# EasyEDA_ir-rgb-controller-chematic.net
KiCad netlist of a schematic drawn in EasyEDA
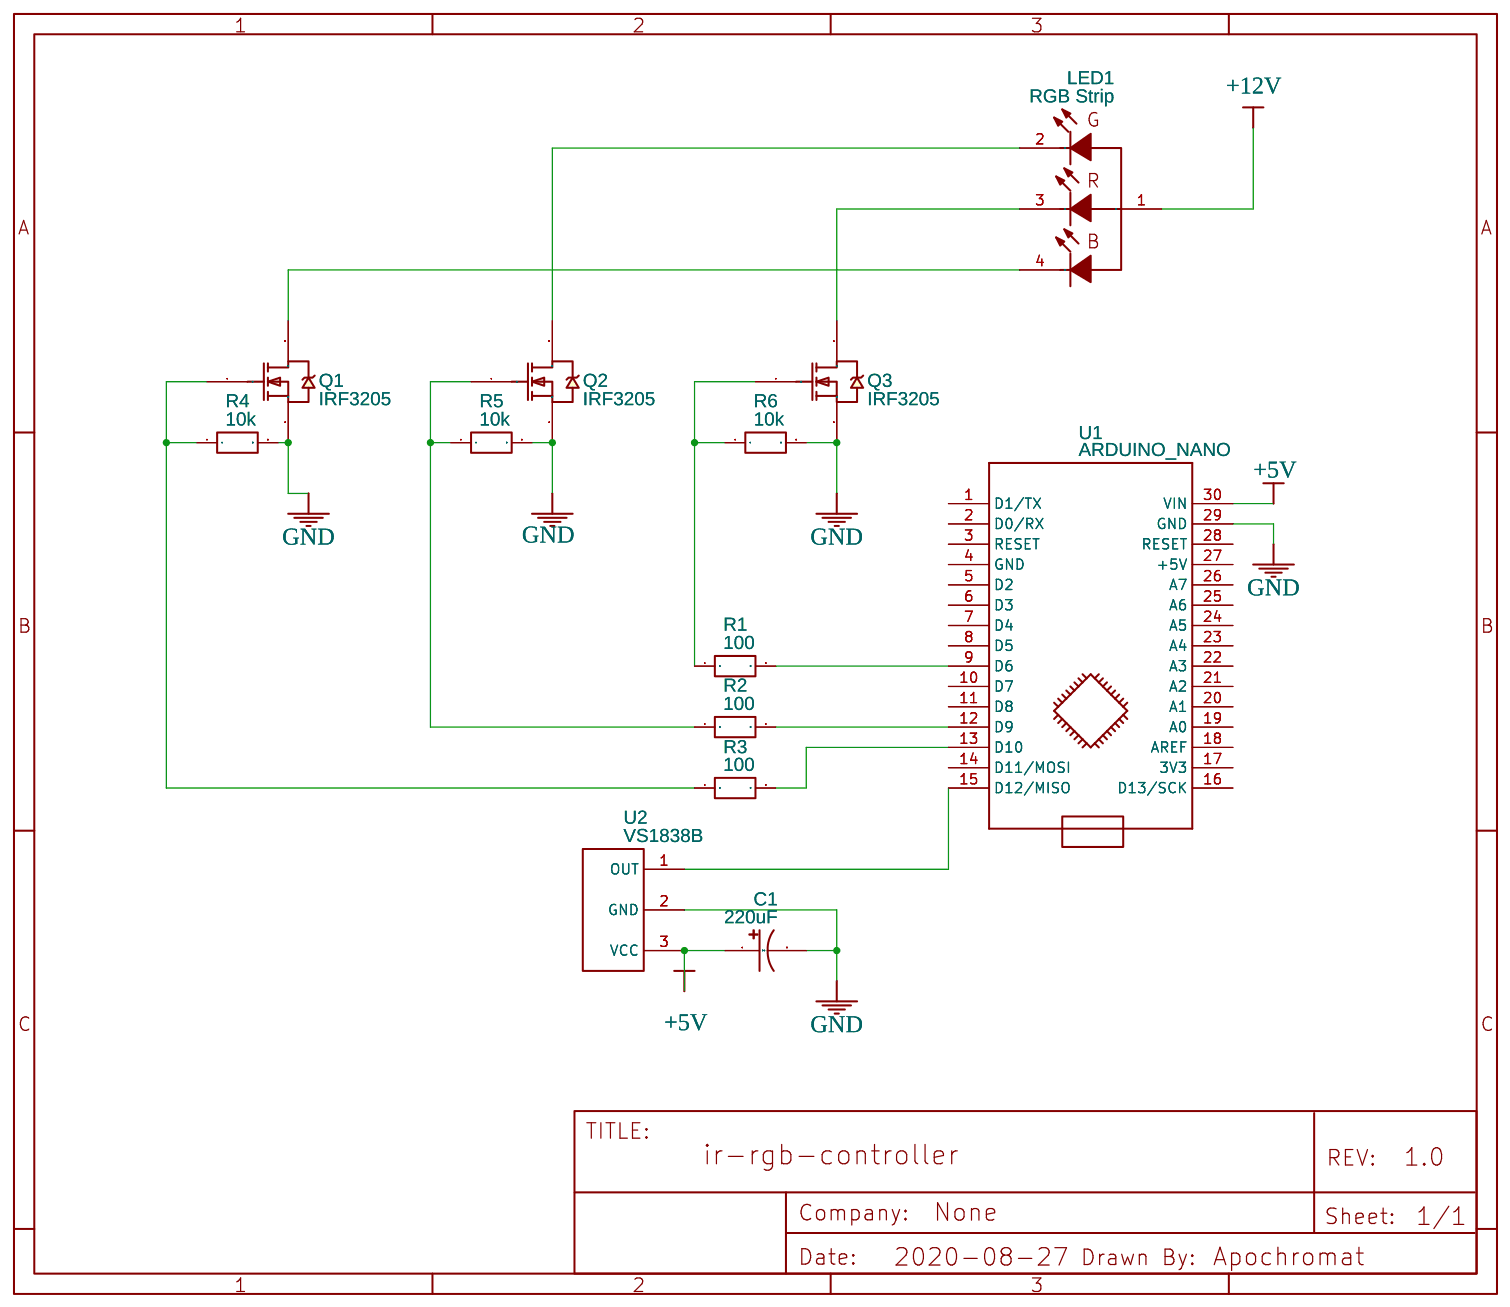
[diagram p0: schematic sheet]

(export (version "E")
  (design (tool "Eeschema 10.0.6"))
  (components
    (comp (ref "C1")
      (value "220uF")
      (fields (field (name "BOM_Supplier Part") "C165659"))
      (libsource (lib "") (part "NHA 25V220uF"))
    )
    (comp (ref "LED1") (value "RGB Strip") (libsource (lib "") (part "RGB Strip")))
    (comp (ref "Q1") (value "IRF3205") (libsource (lib "") (part "IRF3205")))
    (comp (ref "Q2") (value "IRF3205") (libsource (lib "") (part "IRF3205")))
    (comp (ref "Q3") (value "IRF3205") (libsource (lib "") (part "IRF3205")))
    (comp (ref "R1") (value "100") (libsource (lib "") (part "R_AXIAL-0.4_EU")))
    (comp (ref "R2") (value "100") (libsource (lib "") (part "R_AXIAL-0.4_EU")))
    (comp (ref "R3") (value "100") (libsource (lib "") (part "R_AXIAL-0.4_EU")))
    (comp (ref "R4") (value "10k") (libsource (lib "") (part "R_AXIAL-0.4_EU")))
    (comp (ref "R5") (value "10k") (libsource (lib "") (part "R_AXIAL-0.4_EU")))
    (comp (ref "R6") (value "10k") (libsource (lib "") (part "R_AXIAL-0.4_EU")))
    (comp (ref "U1") (value "ARDUINO_NANO") (libsource (lib "") (part "ARDUINO_NANO")))
    (comp (ref "U2") (value "VS1838B") (libsource (lib "") (part "VS1838B")))
  )
  (nets
    (net (code "1") (name "+5V") (class "Default")
      (node (ref "C1") (pin "1") (pinfunction "1_1") (pintype "unspecified"))
      (node (ref "U1") (pin "30") (pinfunction "VIN_30") (pintype "unspecified"))
      (node (ref "U2") (pin "3") (pinfunction "VCC_3") (pintype "unspecified"))
    )
    (net (code "2") (name "+12V") (class "Default")
      (node (ref "LED1") (pin "1") (pinfunction "CA_1") (pintype "unspecified"))
    )
    (net (code "3") (name "GND") (class "Default")
      (node (ref "C1") (pin "2") (pinfunction "2_2") (pintype "unspecified"))
      (node (ref "Q1") (pin "3") (pinfunction "S_3") (pintype "unspecified"))
      (node (ref "Q2") (pin "3") (pinfunction "S_3") (pintype "unspecified"))
      (node (ref "Q3") (pin "3") (pinfunction "S_3") (pintype "unspecified"))
      (node (ref "R4") (pin "2") (pinfunction "2_2") (pintype "unspecified"))
      (node (ref "R5") (pin "2") (pinfunction "2_2") (pintype "unspecified"))
      (node (ref "R6") (pin "2") (pinfunction "2_2") (pintype "unspecified"))
      (node (ref "U1") (pin "29") (pinfunction "GND_29") (pintype "unspecified"))
      (node (ref "U2") (pin "2") (pinfunction "GND_2") (pintype "unspecified"))
    )
    (net (code "4") (name "Net-(LED1-KB)") (class "Default")
      (node (ref "LED1") (pin "4") (pinfunction "KB_4") (pintype "unspecified"))
      (node (ref "Q1") (pin "2") (pinfunction "D_2") (pintype "unspecified"))
    )
    (net (code "5") (name "Net-(LED1-KG)") (class "Default")
      (node (ref "LED1") (pin "2") (pinfunction "KG_2") (pintype "unspecified"))
      (node (ref "Q2") (pin "2") (pinfunction "D_2") (pintype "unspecified"))
    )
    (net (code "6") (name "Net-(LED1-KR)") (class "Default")
      (node (ref "LED1") (pin "3") (pinfunction "KR_3") (pintype "unspecified"))
      (node (ref "Q3") (pin "2") (pinfunction "D_2") (pintype "unspecified"))
    )
    (net (code "7") (name "Net-(Q1-G)") (class "Default")
      (node (ref "Q1") (pin "1") (pinfunction "G_1") (pintype "unspecified"))
      (node (ref "R3") (pin "1") (pinfunction "1_1") (pintype "unspecified"))
      (node (ref "R4") (pin "1") (pinfunction "1_1") (pintype "unspecified"))
    )
    (net (code "8") (name "Net-(Q2-G)") (class "Default")
      (node (ref "Q2") (pin "1") (pinfunction "G_1") (pintype "unspecified"))
      (node (ref "R2") (pin "1") (pinfunction "1_1") (pintype "unspecified"))
      (node (ref "R5") (pin "1") (pinfunction "1_1") (pintype "unspecified"))
    )
    (net (code "9") (name "Net-(Q3-G)") (class "Default")
      (node (ref "Q3") (pin "1") (pinfunction "G_1") (pintype "unspecified"))
      (node (ref "R1") (pin "1") (pinfunction "1_1") (pintype "unspecified"))
      (node (ref "R6") (pin "1") (pinfunction "1_1") (pintype "unspecified"))
    )
    (net (code "10") (name "Net-(U1-D6)") (class "Default")
      (node (ref "R1") (pin "2") (pinfunction "2_2") (pintype "unspecified"))
      (node (ref "U1") (pin "9") (pinfunction "D6_9") (pintype "unspecified"))
    )
    (net (code "11") (name "Net-(U1-D9)") (class "Default")
      (node (ref "R2") (pin "2") (pinfunction "2_2") (pintype "unspecified"))
      (node (ref "U1") (pin "12") (pinfunction "D9_12") (pintype "unspecified"))
    )
    (net (code "12") (name "Net-(U1-D10)") (class "Default")
      (node (ref "R3") (pin "2") (pinfunction "2_2") (pintype "unspecified"))
      (node (ref "U1") (pin "13") (pinfunction "D10_13") (pintype "unspecified"))
    )
    (net (code "13") (name "Net-(U1-D12{slash}MISO)") (class "Default")
      (node (ref "U1") (pin "15") (pinfunction "D12/MISO_15") (pintype "unspecified"))
      (node (ref "U2") (pin "1") (pinfunction "OUT_1") (pintype "unspecified"))
    )
    (net (code "14") (name "unconnected-(U1-+5V-Pad27)") (class "Default")
      (node (ref "U1") (pin "27") (pinfunction "+5V_27") (pintype "unspecified"))
    )
    (net (code "15") (name "unconnected-(U1-3V3-Pad17)") (class "Default")
      (node (ref "U1") (pin "17") (pinfunction "3V3_17") (pintype "unspecified"))
    )
    (net (code "16") (name "unconnected-(U1-A0-Pad19)") (class "Default")
      (node (ref "U1") (pin "19") (pinfunction "A0_19") (pintype "unspecified"))
    )
    (net (code "17") (name "unconnected-(U1-A1-Pad20)") (class "Default")
      (node (ref "U1") (pin "20") (pinfunction "A1_20") (pintype "unspecified"))
    )
    (net (code "18") (name "unconnected-(U1-A2-Pad21)") (class "Default")
      (node (ref "U1") (pin "21") (pinfunction "A2_21") (pintype "unspecified"))
    )
    (net (code "19") (name "unconnected-(U1-A3-Pad22)") (class "Default")
      (node (ref "U1") (pin "22") (pinfunction "A3_22") (pintype "unspecified"))
    )
    (net (code "20") (name "unconnected-(U1-A4-Pad23)") (class "Default")
      (node (ref "U1") (pin "23") (pinfunction "A4_23") (pintype "unspecified"))
    )
    (net (code "21") (name "unconnected-(U1-A5-Pad24)") (class "Default")
      (node (ref "U1") (pin "24") (pinfunction "A5_24") (pintype "unspecified"))
    )
    (net (code "22") (name "unconnected-(U1-A6-Pad25)") (class "Default")
      (node (ref "U1") (pin "25") (pinfunction "A6_25") (pintype "unspecified"))
    )
    (net (code "23") (name "unconnected-(U1-A7-Pad26)") (class "Default")
      (node (ref "U1") (pin "26") (pinfunction "A7_26") (pintype "unspecified"))
    )
    (net (code "24") (name "unconnected-(U1-AREF-Pad18)") (class "Default")
      (node (ref "U1") (pin "18") (pinfunction "AREF_18") (pintype "unspecified"))
    )
    (net (code "25") (name "unconnected-(U1-D0{slash}RX-Pad2)") (class "Default")
      (node (ref "U1") (pin "2") (pinfunction "D0/RX_2") (pintype "unspecified"))
    )
    (net (code "26") (name "unconnected-(U1-D1{slash}TX-Pad1)") (class "Default")
      (node (ref "U1") (pin "1") (pinfunction "D1/TX_1") (pintype "unspecified"))
    )
    (net (code "27") (name "unconnected-(U1-D2-Pad5)") (class "Default")
      (node (ref "U1") (pin "5") (pinfunction "D2_5") (pintype "unspecified"))
    )
    (net (code "28") (name "unconnected-(U1-D3-Pad6)") (class "Default")
      (node (ref "U1") (pin "6") (pinfunction "D3_6") (pintype "unspecified"))
    )
    (net (code "29") (name "unconnected-(U1-D4-Pad7)") (class "Default")
      (node (ref "U1") (pin "7") (pinfunction "D4_7") (pintype "unspecified"))
    )
    (net (code "30") (name "unconnected-(U1-D5-Pad8)") (class "Default")
      (node (ref "U1") (pin "8") (pinfunction "D5_8") (pintype "unspecified"))
    )
    (net (code "31") (name "unconnected-(U1-D7-Pad10)") (class "Default")
      (node (ref "U1") (pin "10") (pinfunction "D7_10") (pintype "unspecified"))
    )
    (net (code "32") (name "unconnected-(U1-D8-Pad11)") (class "Default")
      (node (ref "U1") (pin "11") (pinfunction "D8_11") (pintype "unspecified"))
    )
    (net (code "33") (name "unconnected-(U1-D11{slash}MOSI-Pad14)") (class "Default")
      (node (ref "U1") (pin "14") (pinfunction "D11/MOSI_14") (pintype "unspecified"))
    )
    (net (code "34") (name "unconnected-(U1-D13{slash}SCK-Pad16)") (class "Default")
      (node (ref "U1") (pin "16") (pinfunction "D13/SCK_16") (pintype "unspecified"))
    )
    (net (code "35") (name "unconnected-(U1-GND-Pad4)") (class "Default")
      (node (ref "U1") (pin "4") (pinfunction "GND_4") (pintype "unspecified"))
    )
    (net (code "36") (name "unconnected-(U1-RESET-Pad3)") (class "Default")
      (node (ref "U1") (pin "3") (pinfunction "RESET_3") (pintype "unspecified"))
    )
    (net (code "37") (name "unconnected-(U1-RESET-Pad28)") (class "Default")
      (node (ref "U1") (pin "28") (pinfunction "RESET_28") (pintype "unspecified"))
    )
  )
)
